# Paylaod.net
KiCad netlist of a schematic drawn in Altium Designer
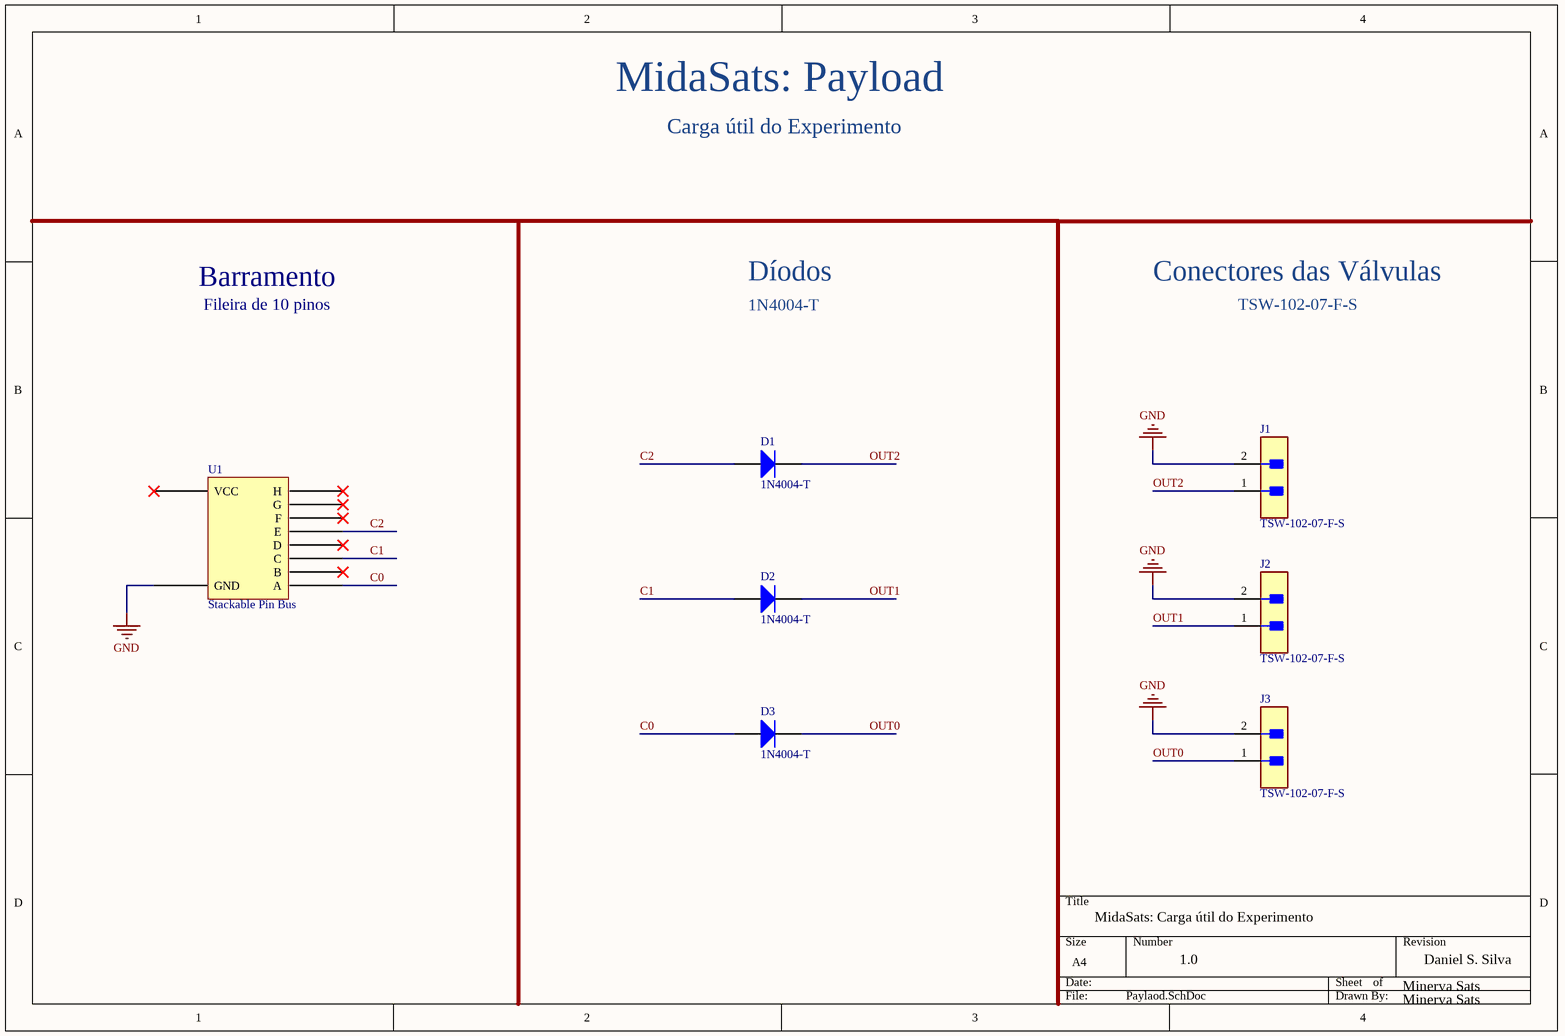
[diagram p0: Paylaod.SchDoc]

(export (version "E")
  (design (tool "Eeschema 10.0.6"))
  (components
    (comp (ref "D1")
      (value "1N4004-T")
      (footprint "DIOD-DO-41-P-2_V")
      (description "1.0 A Rectifier, 15 pF, 400 V, -65 to 150 degC, 2-Pin DO-41 Plastic, RoHS, Tape and Reel")
      (fields (field (name "MANUFACTURER") "Diodes Inc"))
      (libsource (lib "Schlib1") (part "CMP-0639-00014-2"))
    )
    (comp (ref "D2")
      (value "1N4004-T")
      (footprint "DIOD-DO-41-P-2_V")
      (description "1.0 A Rectifier, 15 pF, 400 V, -65 to 150 degC, 2-Pin DO-41 Plastic, RoHS, Tape and Reel")
      (fields (field (name "MANUFACTURER") "Diodes Inc"))
      (libsource (lib "Schlib1") (part "CMP-0639-00014-2"))
    )
    (comp (ref "D3")
      (value "1N4004-T")
      (footprint "DIOD-DO-41-P-2_V")
      (description "1.0 A Rectifier, 15 pF, 400 V, -65 to 150 degC, 2-Pin DO-41 Plastic, RoHS, Tape and Reel")
      (fields (field (name "MANUFACTURER") "Diodes Inc"))
      (libsource (lib "Schlib1") (part "CMP-0639-00014-2"))
    )
    (comp (ref "J1")
      (value "TSW-102-07-F-S")
      (footprint "FP-TSW-102-07-F-S-MFG")
      (description "CONN HEADER VERT 2POS 2.54MM")
      (libsource (lib "Schlib1") (part "CMP-02766-001458-1"))
    )
    (comp (ref "J2")
      (value "TSW-102-07-F-S")
      (footprint "FP-TSW-102-07-F-S-MFG")
      (description "CONN HEADER VERT 2POS 2.54MM")
      (libsource (lib "Schlib1") (part "CMP-02766-001458-1"))
    )
    (comp (ref "J3")
      (value "TSW-102-07-F-S")
      (footprint "FP-TSW-102-07-F-S-MFG")
      (description "CONN HEADER VERT 2POS 2.54MM")
      (libsource (lib "Schlib1") (part "CMP-02766-001458-1"))
    )
    (comp (ref "U1")
      (value "Stackable Pin Bus")
      (footprint "STACKABLE_PIN_BUS")
      (description "10 pinos, Passo 2.54mm, Dimensões da barra 26x2x8mm")
      (libsource (lib "Schlib1") (part "Barramento Empilhável"))
    )
  )
  (nets
    (net (code "1") (name "/C0") (class "Default")
      (node (ref "D3") (pin "1") (pinfunction "A_1") (pintype "passive"))
      (node (ref "U1") (pin "3") (pinfunction "A_3") (pintype "passive"))
    )
    (net (code "2") (name "/C1") (class "Default")
      (node (ref "D2") (pin "1") (pinfunction "A_1") (pintype "passive"))
      (node (ref "U1") (pin "5") (pinfunction "C_5") (pintype "passive"))
    )
    (net (code "3") (name "/C2") (class "Default")
      (node (ref "D1") (pin "1") (pinfunction "A_1") (pintype "passive"))
      (node (ref "U1") (pin "7") (pinfunction "E_7") (pintype "passive"))
    )
    (net (code "4") (name "/OUT0") (class "Default")
      (node (ref "D3") (pin "2") (pinfunction "K_2") (pintype "passive"))
      (node (ref "J3") (pin "1") (pinfunction "1_1") (pintype "passive"))
    )
    (net (code "5") (name "/OUT1") (class "Default")
      (node (ref "D2") (pin "2") (pinfunction "K_2") (pintype "passive"))
      (node (ref "J2") (pin "1") (pinfunction "1_1") (pintype "passive"))
    )
    (net (code "6") (name "/OUT2") (class "Default")
      (node (ref "D1") (pin "2") (pinfunction "K_2") (pintype "passive"))
      (node (ref "J1") (pin "1") (pinfunction "1_1") (pintype "passive"))
    )
    (net (code "7") (name "GND") (class "Default")
      (node (ref "J1") (pin "2") (pinfunction "2_2") (pintype "passive"))
      (node (ref "J2") (pin "2") (pinfunction "2_2") (pintype "passive"))
      (node (ref "J3") (pin "2") (pinfunction "2_2") (pintype "passive"))
      (node (ref "U1") (pin "2") (pinfunction "GND_2") (pintype "passive"))
    )
    (net (code "8") (name "unconnected-(U1-B-Pad4)") (class "Default")
      (node (ref "U1") (pin "4") (pinfunction "B_4") (pintype "passive+no_connect"))
    )
    (net (code "9") (name "unconnected-(U1-D-Pad6)") (class "Default")
      (node (ref "U1") (pin "6") (pinfunction "D_6") (pintype "passive+no_connect"))
    )
    (net (code "10") (name "unconnected-(U1-F-Pad8)") (class "Default")
      (node (ref "U1") (pin "8") (pinfunction "F_8") (pintype "passive+no_connect"))
    )
    (net (code "11") (name "unconnected-(U1-G-Pad9)") (class "Default")
      (node (ref "U1") (pin "9") (pinfunction "G_9") (pintype "passive+no_connect"))
    )
    (net (code "12") (name "unconnected-(U1-H-Pad10)") (class "Default")
      (node (ref "U1") (pin "10") (pinfunction "H_10") (pintype "passive+no_connect"))
    )
    (net (code "13") (name "unconnected-(U1-VCC-Pad1)") (class "Default")
      (node (ref "U1") (pin "1") (pinfunction "VCC_1") (pintype "passive+no_connect"))
    )
  )
)
